# openSX70_EDWIN_V7-9_1_20200228-TSL237T.net
KiCad netlist of a schematic drawn in EAGLE
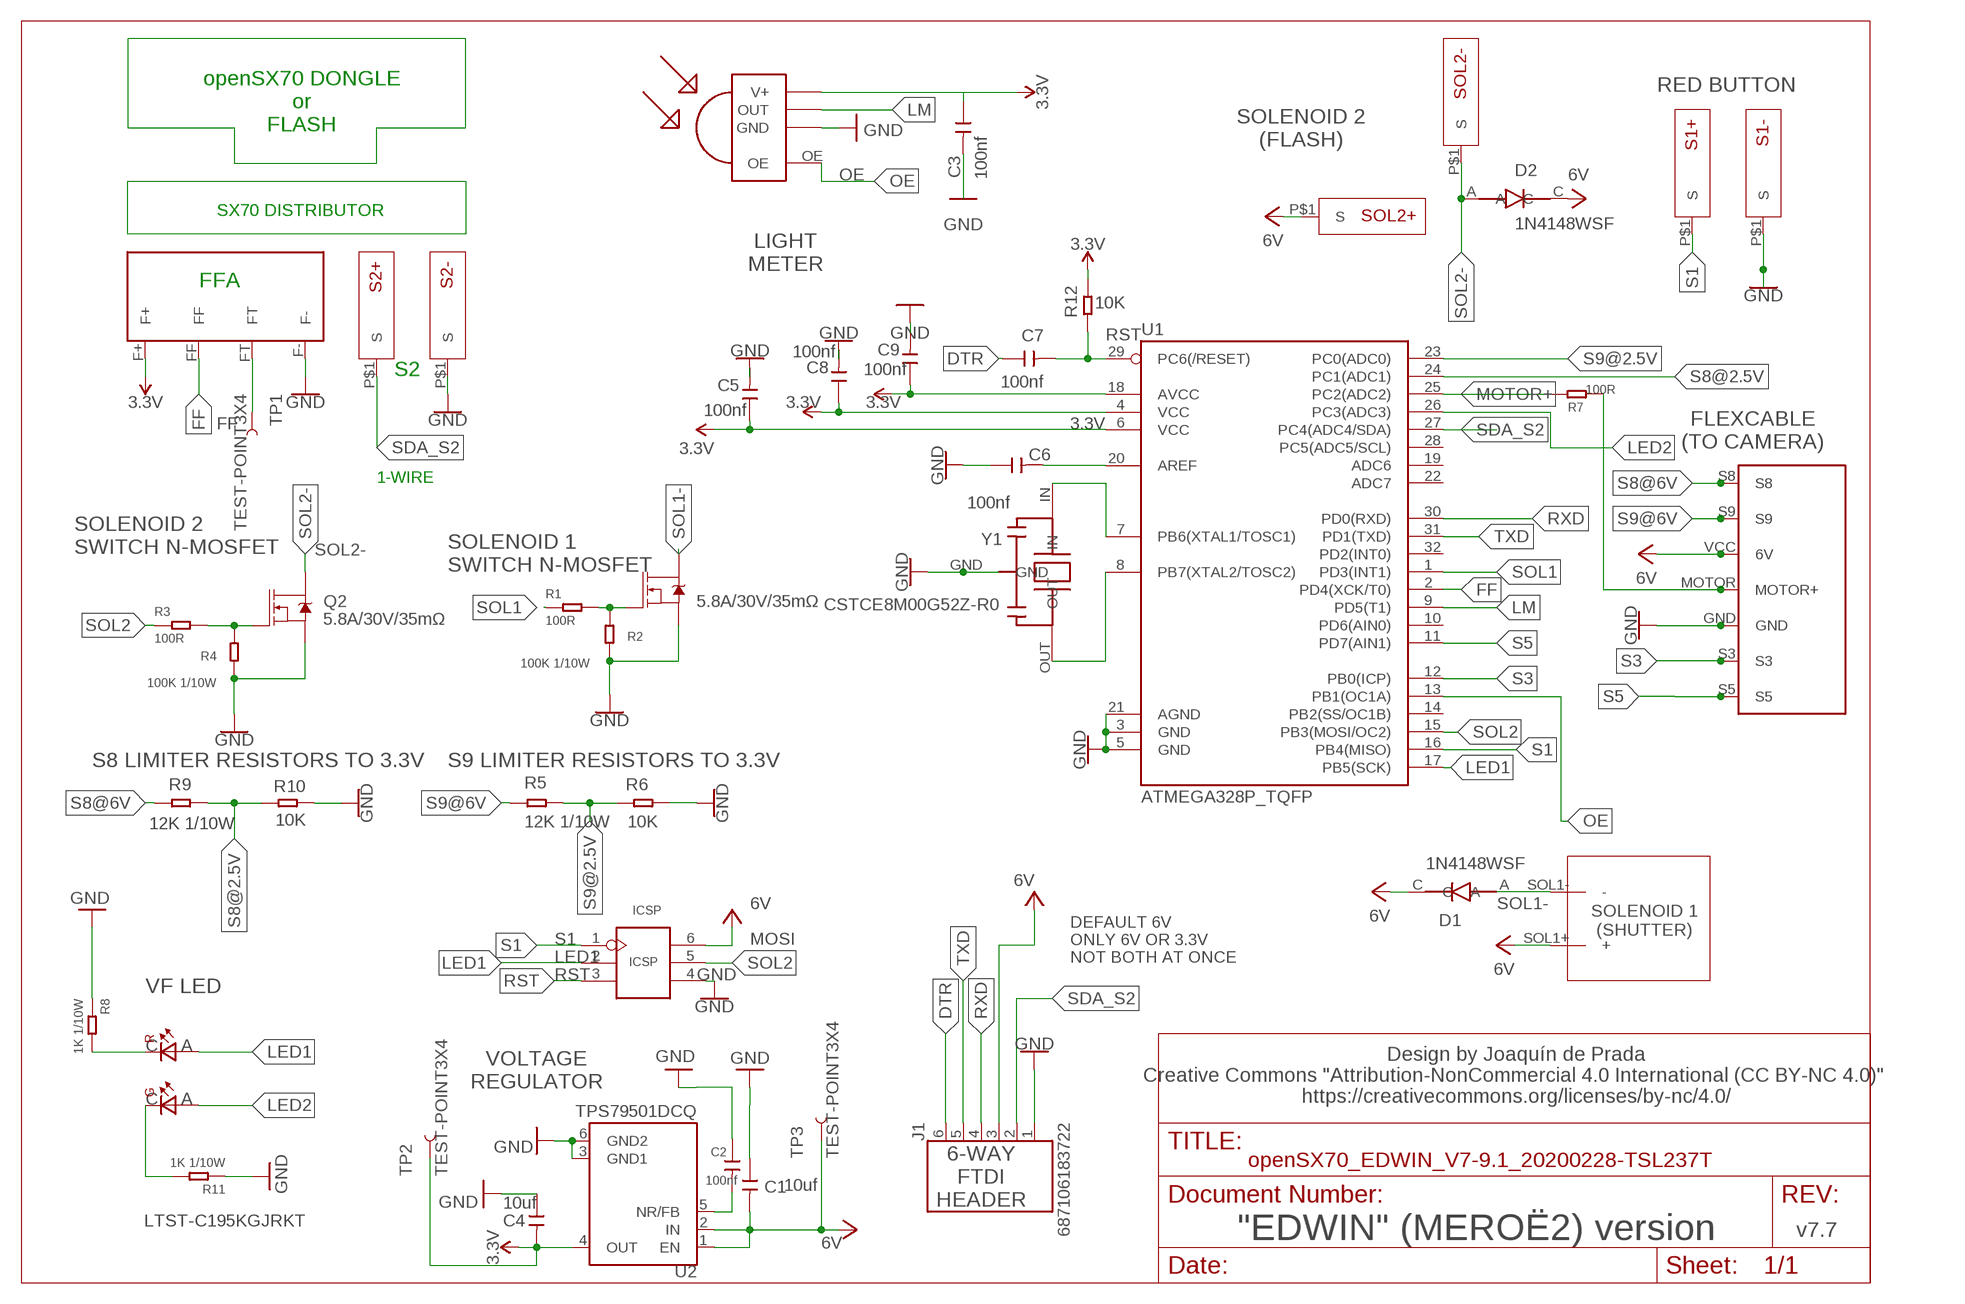
[diagram p0: schematic, sheet 1]

(export (version "E")
  (design (tool "Eeschema 10.0.6"))
  (components
    (comp (ref "C1")
      (value "10uf")
      (footprint "eagle-import:C0603")
      (fields (field (name "MPN") "CC0603KRX5R6BB106"))
      (libsource (lib "eagle-import") (part "CERAMIC-10UF-10V-10%-X5R(0603)"))
    )
    (comp (ref "C2")
      (value "100nf")
      (footprint "eagle-import:C0603")
      (fields (field (name "MPN") "CC0603KRX7R9BB104"))
      (libsource (lib "eagle-import") (part "CERAMIC-100NF-50V-10%-X7R(0603)"))
    )
    (comp (ref "C3")
      (value "100nf")
      (footprint "eagle-import:C0603")
      (fields (field (name "MPN") "CC0603KRX7R9BB104"))
      (libsource (lib "eagle-import") (part "CERAMIC-100NF-50V-10%-X7R(0603)"))
    )
    (comp (ref "C4")
      (value "10uf")
      (footprint "eagle-import:C0603")
      (fields (field (name "MPN") "CC0603KRX5R6BB106"))
      (libsource (lib "eagle-import") (part "CERAMIC-10UF-10V-10%-X5R(0603)"))
    )
    (comp (ref "C5")
      (value "100nf")
      (footprint "eagle-import:C0603")
      (fields (field (name "MPN") "CC0603KRX7R9BB104"))
      (libsource (lib "eagle-import") (part "CERAMIC-100NF-50V-10%-X7R(0603)"))
    )
    (comp (ref "C6")
      (value "100nf")
      (footprint "eagle-import:C0603")
      (fields (field (name "MPN") "CC0603KRX7R9BB104"))
      (libsource (lib "eagle-import") (part "CERAMIC-100NF-50V-10%-X7R(0603)"))
    )
    (comp (ref "C7")
      (value "100nf")
      (footprint "eagle-import:C0603")
      (fields (field (name "MPN") "CC0603KRX7R9BB104"))
      (libsource (lib "eagle-import") (part "CERAMIC-100NF-50V-10%-X7R(0603)"))
    )
    (comp (ref "C8")
      (value "100nf")
      (footprint "eagle-import:C0603")
      (fields (field (name "MPN") "CC0603KRX7R9BB104"))
      (libsource (lib "eagle-import") (part "CERAMIC-100NF-50V-10%-X7R(0603)"))
    )
    (comp (ref "C9")
      (value "100nf")
      (footprint "eagle-import:C0603")
      (fields (field (name "MPN") "CC0603KRX7R9BB104"))
      (libsource (lib "eagle-import") (part "CERAMIC-100NF-50V-10%-X7R(0603)"))
    )
    (comp (ref "D1")
      (value "1N4148WSF")
      (footprint "eagle-import:SODFL2512X100N")
      (fields (field (name "MANUFACTURER") "Fairchild Semiconductor"))
      (libsource (lib "eagle-import") (part "1N4148WS"))
    )
    (comp (ref "D2")
      (value "1N4148WSF")
      (footprint "eagle-import:SODFL2512X100N")
      (fields (field (name "MANUFACTURER") "Fairchild Semiconductor"))
      (libsource (lib "eagle-import") (part "1N4148WS"))
    )
    (comp (ref "ICSP")
      (value "ICSP")
      (footprint "eagle-import:H2X3-2.54")
      (libsource (lib "eagle-import") (part "ICSP"))
    )
    (comp (ref "J1")
      (value "687106183722")
      (footprint "eagle-import:687106183722")
      (fields (field (name "MF") "Wurth Electronics"))
      (libsource (lib "eagle-import") (part "687106183722"))
    )
    (comp (ref "Q1")
      (value "5.8A/30V/35mΩ")
      (footprint "eagle-import:SOT23-3")
      (libsource (lib "eagle-import") (part "MOSFET-NCH-AO3404A"))
    )
    (comp (ref "Q2")
      (value "5.8A/30V/35mΩ")
      (footprint "eagle-import:SOT23-3")
      (libsource (lib "eagle-import") (part "MOSFET-NCH-AO3404A"))
    )
    (comp (ref "R1")
      (value "100R")
      (footprint "eagle-import:R0603")
      (fields (field (name "MPN") "RC0603JR-07100RL"))
      (libsource (lib "eagle-import") (part "SMD-RES-100R-5%-1/10W(0603)"))
    )
    (comp (ref "R2")
      (value "100K 1/10W")
      (footprint "eagle-import:R0603")
      (fields (field (name "MPN") "RC0603JR-07100KL"))
      (libsource (lib "eagle-import") (part "SMD-RES-100K-5%-1/10W(0603)"))
    )
    (comp (ref "R3")
      (value "100R")
      (footprint "eagle-import:R0603")
      (fields (field (name "MPN") "RC0603JR-07100RL"))
      (libsource (lib "eagle-import") (part "SMD-RES-100R-5%-1/10W(0603)"))
    )
    (comp (ref "R4")
      (value "100K 1/10W")
      (footprint "eagle-import:R0603")
      (fields (field (name "MPN") "RC0603JR-07100KL"))
      (libsource (lib "eagle-import") (part "SMD-RES-100K-5%-1/10W(0603)"))
    )
    (comp (ref "R5")
      (value "12K 1/10W")
      (footprint "eagle-import:R0603")
      (fields (field (name "MPN") "RC0603FR-0715KL"))
      (libsource (lib "eagle-import") (part "SMD-RES-15K-1%-1/10W(0603)"))
    )
    (comp (ref "R6")
      (value "10K")
      (footprint "eagle-import:R0603")
      (fields (field (name "MPN") "RC0603FR-0710KL"))
      (libsource (lib "eagle-import") (part "SMD-RES-10K-1%-1/10W(0603)"))
    )
    (comp (ref "R7")
      (value "100R")
      (footprint "eagle-import:R0603")
      (fields (field (name "MPN") "RC0603JR-07100RL"))
      (libsource (lib "eagle-import") (part "SMD-RES-100R-5%-1/10W(0603)"))
    )
    (comp (ref "R8")
      (value "1K 1/10W")
      (footprint "eagle-import:R0603")
      (fields (field (name "MPN") "RC0603JR-071KL"))
      (libsource (lib "eagle-import") (part "SMD-RES-1K-5%-1/10W(0603)"))
    )
    (comp (ref "R9")
      (value "12K 1/10W")
      (footprint "eagle-import:R0603")
      (fields (field (name "MPN") "RC0603FR-0715KL"))
      (libsource (lib "eagle-import") (part "SMD-RES-15K-1%-1/10W(0603)"))
    )
    (comp (ref "R10")
      (value "10K")
      (footprint "eagle-import:R0603")
      (fields (field (name "MPN") "RC0603FR-0710KL"))
      (libsource (lib "eagle-import") (part "SMD-RES-10K-1%-1/10W(0603)"))
    )
    (comp (ref "R11")
      (value "1K 1/10W")
      (footprint "eagle-import:R0603")
      (fields (field (name "MPN") "RC0603JR-071KL"))
      (libsource (lib "eagle-import") (part "SMD-RES-1K-5%-1/10W(0603)"))
    )
    (comp (ref "R12")
      (value "10K")
      (footprint "eagle-import:R0603")
      (fields (field (name "MPN") "RC0603FR-0710KL"))
      (libsource (lib "eagle-import") (part "SMD-RES-10K-1%-1/10W(0603)"))
    )
    (comp (ref "S1+")
      (value "SX70-S-PAD-NEW")
      (footprint "eagle-import:SX70-S-PAD2")
      (libsource (lib "eagle-import") (part "SX70-S-PAD-NEW"))
    )
    (comp (ref "S1-")
      (value "SX70-S-PAD-NEW")
      (footprint "eagle-import:SX70-S-PAD2")
      (libsource (lib "eagle-import") (part "SX70-S-PAD-NEW"))
    )
    (comp (ref "S2+")
      (value "SX70-S-PAD-NEW")
      (footprint "eagle-import:SX70-S-PAD2")
      (libsource (lib "eagle-import") (part "SX70-S-PAD-NEW"))
    )
    (comp (ref "S2-")
      (value "SX70-S-PAD-NEW")
      (footprint "eagle-import:SX70-S-PAD2")
      (libsource (lib "eagle-import") (part "SX70-S-PAD-NEW"))
    )
    (comp (ref "SOL1")
      (value "SX70-SOLENOID1-2PADS")
      (footprint "eagle-import:SX70-SOLENOID1-2")
      (libsource (lib "eagle-import") (part "SX70-SOLENOID1-2PADS"))
    )
    (comp (ref "SOL2+")
      (value "SX70-S-PAD-NEW")
      (footprint "eagle-import:SX70-S-PAD2")
      (libsource (lib "eagle-import") (part "SX70-S-PAD-NEW"))
    )
    (comp (ref "SOL2-")
      (value "SX70-S-PAD-NEW")
      (footprint "eagle-import:SX70-S-PAD2")
      (libsource (lib "eagle-import") (part "SX70-S-PAD-NEW"))
    )
    (comp (ref "TP1")
      (value "TEST-POINT3X4")
      (footprint "eagle-import:PAD.03X.04")
      (libsource (lib "eagle-import") (part "TEST-POINT3X4"))
    )
    (comp (ref "TP2")
      (value "TEST-POINT3X4")
      (footprint "eagle-import:PAD.03X.04")
      (libsource (lib "eagle-import") (part "TEST-POINT3X4"))
    )
    (comp (ref "TP3")
      (value "TEST-POINT3X4")
      (footprint "eagle-import:PAD.03X.04")
      (libsource (lib "eagle-import") (part "TEST-POINT3X4"))
    )
    (comp (ref "U$1")
      (value "SX70-7-PAD")
      (footprint "eagle-import:SX70-7-PAD-PROPER")
      (libsource (lib "eagle-import") (part "SX70-7-PAD"))
    )
    (comp (ref "U$2")
      (value "FFA")
      (footprint "eagle-import:FFA-PAD-PACKAGE")
      (libsource (lib "eagle-import") (part "SX70-FFA-PAD"))
    )
    (comp (ref "U$3")
      (value "TSL237T")
      (footprint "eagle-import:TSL237T")
      (libsource (lib "eagle-import") (part "TSL237T"))
    )
    (comp (ref "U$4")
      (value "LTST-C195KGJRKT")
      (footprint "eagle-import:LTST-BILED-15X16")
      (fields (field (name "MF") "Lite-On Inc."))
      (libsource (lib "eagle-import") (part "LTST-C195KGJRKT"))
    )
    (comp (ref "U1")
      (value "ATMEGA328P_TQFP")
      (footprint "eagle-import:TQFP32-08")
      (libsource (lib "eagle-import") (part "ATMEGA328P_TQFP"))
    )
    (comp (ref "U2")
      (value "TPS79501DCQ")
      (footprint "eagle-import:SOT127P706X180-6N")
      (fields (field (name "DIGI-KEY_PART_NUMBER") "296-27102-5-ND") (field (name "MF") "Texas Instruments"))
      (libsource (lib "eagle-import") (part "TPS79501DCQ"))
    )
    (comp (ref "Y1")
      (value "CSTCE8M00G52Z-R0")
      (footprint "eagle-import:CFP95P160X100-3N")
      (fields (field (name "MF") "Murata") (field (name "MP") "CSTCE16M0V53-R0"))
      (libsource (lib "eagle-import") (part "CSTCE16M0V53-R0"))
    )
  )
  (nets
    (net (code "1") (name "3.3V") (class "Default")
      (node (ref "C3") (pin "1") (pinfunction "1_1") (pintype "passive"))
      (node (ref "C4") (pin "2") (pinfunction "2_2") (pintype "passive"))
      (node (ref "C5") (pin "1") (pinfunction "1_1") (pintype "passive"))
      (node (ref "C8") (pin "1") (pinfunction "1_1") (pintype "passive"))
      (node (ref "C9") (pin "1") (pinfunction "1_1") (pintype "passive"))
      (node (ref "R12") (pin "2") (pinfunction "2_2") (pintype "passive"))
      (node (ref "TP2") (pin "P$1") (pinfunction "1_P$1") (pintype "bidirectional"))
      (node (ref "U$2") (pin "F+") (pinfunction "F+_F+") (pintype "bidirectional"))
      (node (ref "U$3") (pin "VDD") (pinfunction "V+_VDD") (pintype "bidirectional"))
      (node (ref "U1") (pin "18") (pinfunction "AVCC_18") (pintype "bidirectional"))
      (node (ref "U1") (pin "4") (pinfunction "VCC_4") (pintype "bidirectional"))
      (node (ref "U1") (pin "6") (pinfunction "VCC_6") (pintype "bidirectional"))
      (node (ref "U2") (pin "4") (pinfunction "OUT_4") (pintype "output"))
    )
    (net (code "2") (name "6V") (class "Default")
      (node (ref "C1") (pin "2") (pinfunction "2_2") (pintype "passive"))
      (node (ref "D1") (pin "C") (pinfunction "C_C") (pintype "passive"))
      (node (ref "D2") (pin "C") (pinfunction "C_C") (pintype "passive"))
      (node (ref "ICSP") (pin "6") (pinfunction "VCC_6") (pintype "bidirectional"))
      (node (ref "J1") (pin "3") (pinfunction "4_3") (pintype "passive"))
      (node (ref "SOL1") (pin "SOL1+") (pinfunction "+_SOL1+") (pintype "bidirectional"))
      (node (ref "SOL2+") (pin "P$1") (pinfunction "S_P$1") (pintype "bidirectional"))
      (node (ref "TP3") (pin "P$1") (pinfunction "1_P$1") (pintype "bidirectional"))
      (node (ref "U$1") (pin "VCC") (pinfunction "6V_VCC") (pintype "bidirectional"))
      (node (ref "U2") (pin "1") (pinfunction "EN_1") (pintype "input"))
      (node (ref "U2") (pin "2") (pinfunction "IN_2") (pintype "input"))
    )
    (net (code "3") (name "DTR") (class "Default")
      (node (ref "C7") (pin "1") (pinfunction "1_1") (pintype "passive"))
      (node (ref "J1") (pin "6") (pinfunction "1_6") (pintype "passive"))
    )
    (net (code "4") (name "FF") (class "Default")
      (node (ref "U$2") (pin "FF") (pinfunction "FF_FF") (pintype "bidirectional"))
      (node (ref "U1") (pin "2") (pinfunction "PD4(XCK/T0)_2") (pintype "bidirectional"))
    )
    (net (code "5") (name "GND") (class "Default")
      (node (ref "C1") (pin "1") (pinfunction "1_1") (pintype "passive"))
      (node (ref "C2") (pin "1") (pinfunction "1_1") (pintype "passive"))
      (node (ref "C3") (pin "2") (pinfunction "2_2") (pintype "passive"))
      (node (ref "C4") (pin "1") (pinfunction "1_1") (pintype "passive"))
      (node (ref "C5") (pin "2") (pinfunction "2_2") (pintype "passive"))
      (node (ref "C6") (pin "1") (pinfunction "1_1") (pintype "passive"))
      (node (ref "C8") (pin "2") (pinfunction "2_2") (pintype "passive"))
      (node (ref "C9") (pin "2") (pinfunction "2_2") (pintype "passive"))
      (node (ref "ICSP") (pin "4") (pinfunction "GND_4") (pintype "bidirectional"))
      (node (ref "J1") (pin "1") (pinfunction "6_1") (pintype "passive"))
      (node (ref "Q1") (pin "2") (pinfunction "S_2") (pintype "bidirectional"))
      (node (ref "Q2") (pin "2") (pinfunction "S_2") (pintype "bidirectional"))
      (node (ref "R10") (pin "2") (pinfunction "2_2") (pintype "passive"))
      (node (ref "R11") (pin "1") (pinfunction "1_1") (pintype "passive"))
      (node (ref "R2") (pin "1") (pinfunction "1_1") (pintype "passive"))
      (node (ref "R4") (pin "1") (pinfunction "1_1") (pintype "passive"))
      (node (ref "R6") (pin "2") (pinfunction "2_2") (pintype "passive"))
      (node (ref "R8") (pin "1") (pinfunction "1_1") (pintype "passive"))
      (node (ref "S1-") (pin "P$1") (pinfunction "S_P$1") (pintype "bidirectional"))
      (node (ref "S2-") (pin "P$1") (pinfunction "S_P$1") (pintype "bidirectional"))
      (node (ref "U$1") (pin "GND") (pinfunction "GND_GND") (pintype "bidirectional"))
      (node (ref "U$2") (pin "F-") (pinfunction "F-_F-") (pintype "bidirectional"))
      (node (ref "U$3") (pin "GND") (pinfunction "GND_GND") (pintype "bidirectional"))
      (node (ref "U1") (pin "21") (pinfunction "AGND_21") (pintype "bidirectional"))
      (node (ref "U1") (pin "3") (pinfunction "GND_3") (pintype "bidirectional"))
      (node (ref "U1") (pin "5") (pinfunction "GND_5") (pintype "bidirectional"))
      (node (ref "U2") (pin "3") (pinfunction "GND1_3") (pintype "power_in"))
      (node (ref "U2") (pin "6") (pinfunction "GND2_6") (pintype "power_in"))
      (node (ref "Y1") (pin "GND") (pinfunction "GND_GND") (pintype "passive"))
    )
    (net (code "6") (name "LED1") (class "Default")
      (node (ref "ICSP") (pin "2") (pinfunction "SCK_2") (pintype "bidirectional"))
      (node (ref "U$4") (pin "P$2") (pinfunction "A2_P$2") (pintype "passive"))
      (node (ref "U1") (pin "17") (pinfunction "PB5(SCK)_17") (pintype "bidirectional"))
    )
    (net (code "7") (name "LED2") (class "Default")
      (node (ref "U$4") (pin "P$1") (pinfunction "A1_P$1") (pintype "passive"))
      (node (ref "U1") (pin "26") (pinfunction "PC3(ADC3)_26") (pintype "bidirectional"))
    )
    (net (code "8") (name "LM") (class "Default")
      (node (ref "U$3") (pin "OUT") (pinfunction "OUT_OUT") (pintype "bidirectional"))
      (node (ref "U1") (pin "9") (pinfunction "PD5(T1)_9") (pintype "bidirectional"))
    )
    (net (code "9") (name "MOTOR+") (class "Default")
      (node (ref "R7") (pin "1") (pinfunction "1_1") (pintype "passive"))
      (node (ref "U1") (pin "25") (pinfunction "PC2(ADC2)_25") (pintype "bidirectional"))
    )
    (net (code "10") (name "Net-(Q1-G)") (class "Default")
      (node (ref "Q1") (pin "1") (pinfunction "G_1") (pintype "bidirectional"))
      (node (ref "R1") (pin "2") (pinfunction "2_2") (pintype "passive"))
      (node (ref "R2") (pin "2") (pinfunction "2_2") (pintype "passive"))
    )
    (net (code "11") (name "Net-(Q2-G)") (class "Default")
      (node (ref "Q2") (pin "1") (pinfunction "G_1") (pintype "bidirectional"))
      (node (ref "R3") (pin "2") (pinfunction "2_2") (pintype "passive"))
      (node (ref "R4") (pin "2") (pinfunction "2_2") (pintype "passive"))
    )
    (net (code "12") (name "Net-(TP1-1)") (class "Default")
      (node (ref "TP1") (pin "P$1") (pinfunction "1_P$1") (pintype "bidirectional"))
      (node (ref "U$2") (pin "FT") (pinfunction "FT_FT") (pintype "bidirectional"))
    )
    (net (code "13") (name "Net-(U$1-MOTOR+)") (class "Default")
      (node (ref "R7") (pin "2") (pinfunction "2_2") (pintype "passive"))
      (node (ref "U$1") (pin "MOTOR") (pinfunction "MOTOR+_MOTOR") (pintype "bidirectional"))
    )
    (net (code "14") (name "Net-(U$4-K1)") (class "Default")
      (node (ref "R11") (pin "2") (pinfunction "2_2") (pintype "passive"))
      (node (ref "U$4") (pin "P$3") (pinfunction "K1_P$3") (pintype "passive"))
    )
    (net (code "15") (name "Net-(U$4-K2)") (class "Default")
      (node (ref "R8") (pin "2") (pinfunction "2_2") (pintype "passive"))
      (node (ref "U$4") (pin "P$4") (pinfunction "K2_P$4") (pintype "passive"))
    )
    (net (code "16") (name "Net-(U1-AREF)") (class "Default")
      (node (ref "C6") (pin "2") (pinfunction "2_2") (pintype "passive"))
      (node (ref "U1") (pin "20") (pinfunction "AREF_20") (pintype "bidirectional"))
    )
    (net (code "17") (name "Net-(U1-PB6(XTAL1{slash}TOSC1))") (class "Default")
      (node (ref "U1") (pin "7") (pinfunction "PB6(XTAL1/TOSC1)_7") (pintype "bidirectional"))
      (node (ref "Y1") (pin "IN") (pinfunction "IN_IN") (pintype "input"))
    )
    (net (code "18") (name "Net-(U1-PB7(XTAL2{slash}TOSC2))") (class "Default")
      (node (ref "U1") (pin "8") (pinfunction "PB7(XTAL2/TOSC2)_8") (pintype "bidirectional"))
      (node (ref "Y1") (pin "OUT") (pinfunction "OUT_OUT") (pintype "output"))
    )
    (net (code "19") (name "Net-(U2-NR{slash}FB)") (class "Default")
      (node (ref "C2") (pin "2") (pinfunction "2_2") (pintype "passive"))
      (node (ref "U2") (pin "5") (pinfunction "NR/FB_5") (pintype "input"))
    )
    (net (code "20") (name "OE") (class "Default")
      (node (ref "U$3") (pin "OE") (pinfunction "OE_OE") (pintype "bidirectional"))
      (node (ref "U1") (pin "13") (pinfunction "PB1(OC1A)_13") (pintype "bidirectional"))
    )
    (net (code "21") (name "RST") (class "Default")
      (node (ref "C7") (pin "2") (pinfunction "2_2") (pintype "passive"))
      (node (ref "ICSP") (pin "3") (pinfunction "RST_3") (pintype "bidirectional"))
      (node (ref "R12") (pin "1") (pinfunction "1_1") (pintype "passive"))
      (node (ref "U1") (pin "29") (pinfunction "PC6(/RESET)_29") (pintype "bidirectional"))
    )
    (net (code "22") (name "RXD") (class "Default")
      (node (ref "J1") (pin "4") (pinfunction "3_4") (pintype "passive"))
      (node (ref "U1") (pin "30") (pinfunction "PD0(RXD)_30") (pintype "bidirectional"))
    )
    (net (code "23") (name "S1") (class "Default")
      (node (ref "ICSP") (pin "1") (pinfunction "MISO_1") (pintype "bidirectional"))
      (node (ref "S1+") (pin "P$1") (pinfunction "S_P$1") (pintype "bidirectional"))
      (node (ref "U1") (pin "16") (pinfunction "PB4(MISO)_16") (pintype "bidirectional"))
    )
    (net (code "24") (name "S3") (class "Default")
      (node (ref "U$1") (pin "S3") (pinfunction "S3_S3") (pintype "bidirectional"))
      (node (ref "U1") (pin "12") (pinfunction "PB0(ICP)_12") (pintype "bidirectional"))
    )
    (net (code "25") (name "S5") (class "Default")
      (node (ref "U$1") (pin "S5") (pinfunction "S5_S5") (pintype "bidirectional"))
      (node (ref "U1") (pin "11") (pinfunction "PD7(AIN1)_11") (pintype "bidirectional"))
    )
    (net (code "26") (name "S8@2.5V") (class "Default")
      (node (ref "R10") (pin "1") (pinfunction "1_1") (pintype "passive"))
      (node (ref "R9") (pin "2") (pinfunction "2_2") (pintype "passive"))
      (node (ref "U1") (pin "24") (pinfunction "PC1(ADC1)_24") (pintype "bidirectional"))
    )
    (net (code "27") (name "S8@6V") (class "Default")
      (node (ref "R9") (pin "1") (pinfunction "1_1") (pintype "passive"))
      (node (ref "U$1") (pin "S8") (pinfunction "S8_S8") (pintype "bidirectional"))
    )
    (net (code "28") (name "S9@2.5V") (class "Default")
      (node (ref "R5") (pin "2") (pinfunction "2_2") (pintype "passive"))
      (node (ref "R6") (pin "1") (pinfunction "1_1") (pintype "passive"))
      (node (ref "U1") (pin "23") (pinfunction "PC0(ADC0)_23") (pintype "bidirectional"))
    )
    (net (code "29") (name "S9@6V") (class "Default")
      (node (ref "R5") (pin "1") (pinfunction "1_1") (pintype "passive"))
      (node (ref "U$1") (pin "S9") (pinfunction "S9_S9") (pintype "bidirectional"))
    )
    (net (code "30") (name "SDA_S2") (class "Default")
      (node (ref "J1") (pin "2") (pinfunction "5_2") (pintype "passive"))
      (node (ref "S2+") (pin "P$1") (pinfunction "S_P$1") (pintype "bidirectional"))
      (node (ref "U1") (pin "27") (pinfunction "PC4(ADC4/SDA)_27") (pintype "bidirectional"))
    )
    (net (code "31") (name "SOL1") (class "Default")
      (node (ref "R1") (pin "1") (pinfunction "1_1") (pintype "passive"))
      (node (ref "U1") (pin "1") (pinfunction "PD3(INT1)_1") (pintype "bidirectional"))
    )
    (net (code "32") (name "SOL1-") (class "Default")
      (node (ref "D1") (pin "A") (pinfunction "A_A") (pintype "passive"))
      (node (ref "Q1") (pin "3") (pinfunction "D_3") (pintype "bidirectional"))
      (node (ref "SOL1") (pin "SOL1-") (pinfunction "-_SOL1-") (pintype "bidirectional"))
    )
    (net (code "33") (name "SOL2") (class "Default")
      (node (ref "ICSP") (pin "5") (pinfunction "MOSI_5") (pintype "bidirectional"))
      (node (ref "R3") (pin "1") (pinfunction "1_1") (pintype "passive"))
      (node (ref "U1") (pin "15") (pinfunction "PB3(MOSI/OC2)_15") (pintype "bidirectional"))
    )
    (net (code "34") (name "SOL2-") (class "Default")
      (node (ref "D2") (pin "A") (pinfunction "A_A") (pintype "passive"))
      (node (ref "Q2") (pin "3") (pinfunction "D_3") (pintype "bidirectional"))
      (node (ref "SOL2-") (pin "P$1") (pinfunction "S_P$1") (pintype "bidirectional"))
    )
    (net (code "35") (name "TXD") (class "Default")
      (node (ref "J1") (pin "5") (pinfunction "2_5") (pintype "passive"))
      (node (ref "U1") (pin "31") (pinfunction "PD1(TXD)_31") (pintype "bidirectional"))
    )
    (net (code "36") (name "unconnected-(U1-ADC6-Pad19)") (class "Default")
      (node (ref "U1") (pin "19") (pinfunction "ADC6_19") (pintype "bidirectional"))
    )
    (net (code "37") (name "unconnected-(U1-ADC7-Pad22)") (class "Default")
      (node (ref "U1") (pin "22") (pinfunction "ADC7_22") (pintype "bidirectional"))
    )
    (net (code "38") (name "unconnected-(U1-PB2(SS{slash}OC1B)-Pad14)") (class "Default")
      (node (ref "U1") (pin "14") (pinfunction "PB2(SS/OC1B)_14") (pintype "bidirectional"))
    )
    (net (code "39") (name "unconnected-(U1-PC5(ADC5{slash}SCL)-Pad28)") (class "Default")
      (node (ref "U1") (pin "28") (pinfunction "PC5(ADC5/SCL)_28") (pintype "bidirectional"))
    )
    (net (code "40") (name "unconnected-(U1-PD2(INT0)-Pad32)") (class "Default")
      (node (ref "U1") (pin "32") (pinfunction "PD2(INT0)_32") (pintype "bidirectional"))
    )
    (net (code "41") (name "unconnected-(U1-PD6(AIN0)-Pad10)") (class "Default")
      (node (ref "U1") (pin "10") (pinfunction "PD6(AIN0)_10") (pintype "bidirectional"))
    )
  )
)
